# Almazny_channel.net
KiCad netlist of a schematic drawn in Altium Designer
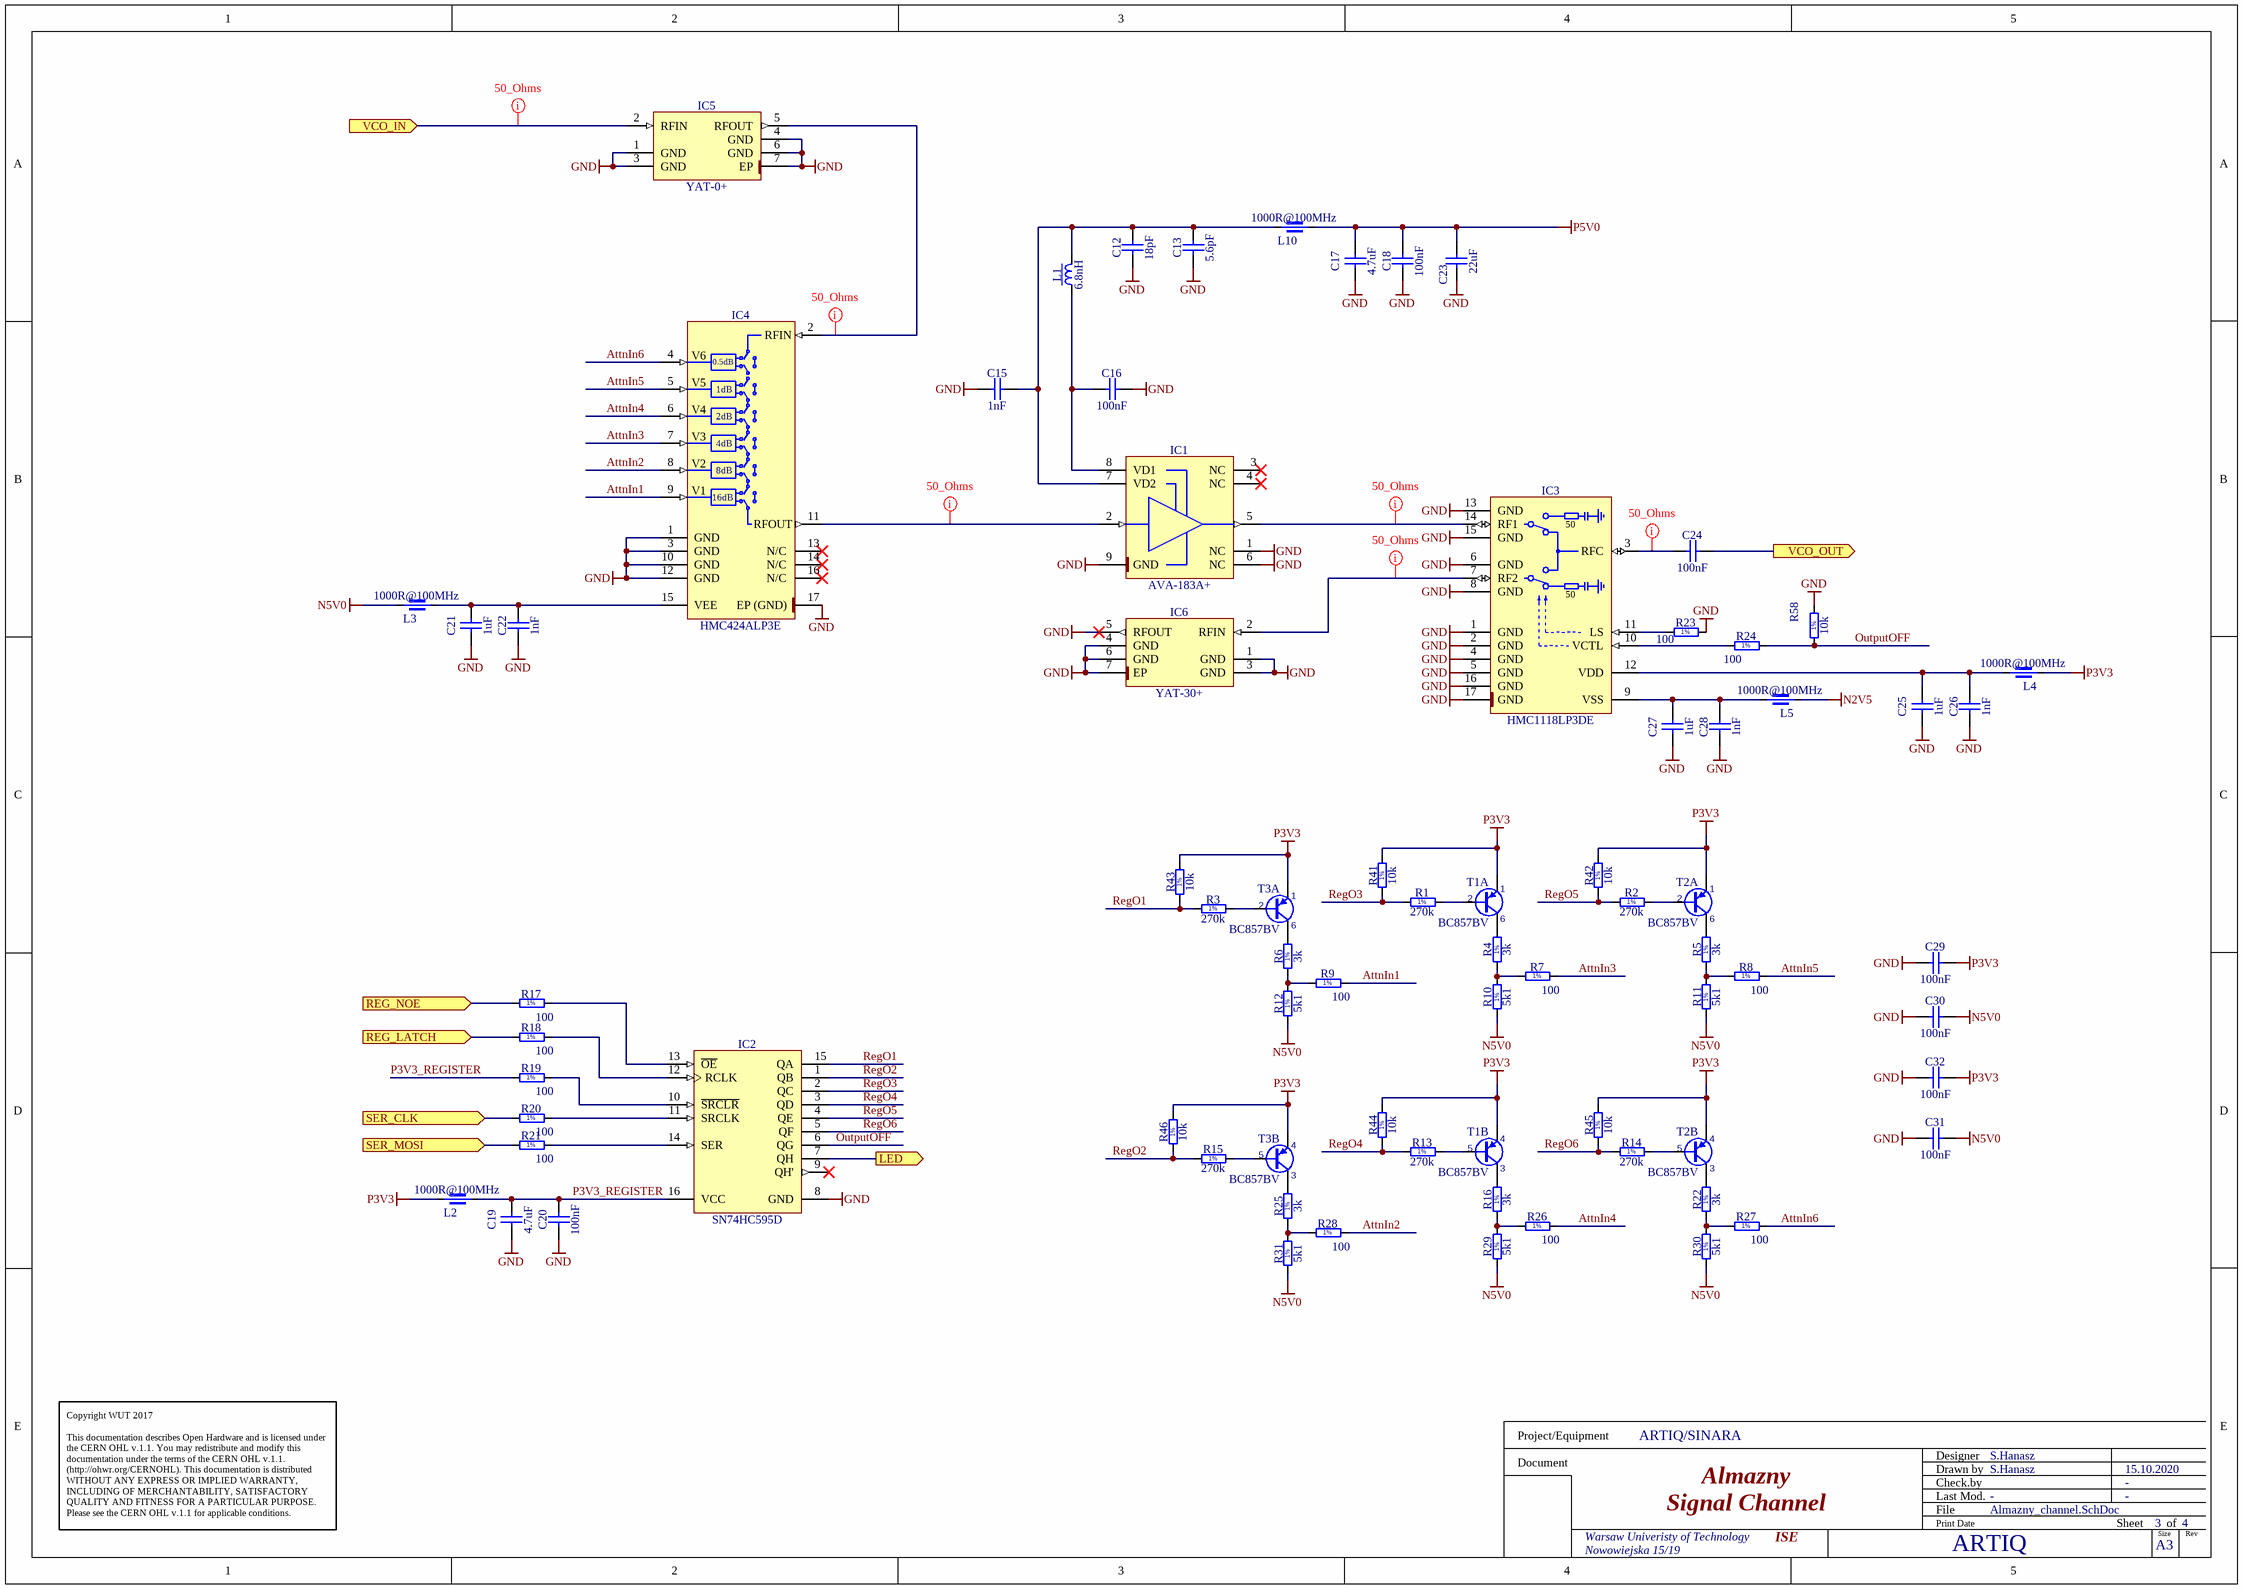
[diagram p0: Almazny_channel.SchDoc]

(export (version "E")
  (design (tool "Eeschema 10.0.6"))
  (components
    (comp (ref "C12")
      (value "18pF")
      (footprint "CAPC1005X55N")
      (description "Non-polarised capacitor")
      (fields
        (field (name "PART NUMBER") "CC0402_18PF_50V_5%_C0G")
        (field (name "VOLTAGE") "50V")
        (field (name "AUTHOR") "CERN DEM JLC")
      )
      (libsource (lib "Capacitors") (part "Capacitor - non polarized"))
    )
    (comp (ref "C13")
      (value "5.6pF")
      (footprint "CAPC1005X61N")
      (description "Non-polarised capacitor")
      (fields
        (field (name "PART NUMBER") "CC0402_5.6PF_50V_0.1PF_NP0_JOHANSON_R07S")
        (field (name "VOLTAGE") "50V")
        (field (name "AUTHOR") "CERN DEM MR")
      )
      (libsource (lib "Capacitors") (part "Capacitor - non polarized"))
    )
    (comp (ref "C15")
      (value "1nF")
      (footprint "CAPC1005X55N")
      (description "Non-polarised capacitor")
      (fields
        (field (name "PART NUMBER") "CC0402_1NF_50V_10%_X7R")
        (field (name "VOLTAGE") "50V")
        (field (name "AUTHOR") "CERN DEM JLC")
      )
      (libsource (lib "Capacitors") (part "Capacitor - non polarized"))
    )
    (comp (ref "C16")
      (value "100nF")
      (footprint "CAPC1005X55N")
      (description "Non-polarised capacitor")
      (fields
        (field (name "PART NUMBER") "CC0402_100NF_16V_10%_X5R")
        (field (name "VOLTAGE") "16V")
        (field (name "AUTHOR") "CERN DEM JLC")
      )
      (libsource (lib "Capacitors") (part "Capacitor - non polarized"))
    )
    (comp (ref "C17")
      (value "4.7uF")
      (footprint "CAPC1709X95N")
      (description "Non-polarised capacitor")
      (fields
        (field (name "MANUFACTURER") "GENERIC")
        (field (name "MANUFACTURER PART NUMBER") "CC0603_4.7UF_16V_10%_X5R")
        (field (name "AUTHOR") "CERN DEM JLC")
      )
      (libsource (lib "Capacitors") (part "Capacitor - non polarized"))
    )
    (comp (ref "C18")
      (value "100nF")
      (footprint "CAPC1005X55N")
      (description "Non-polarised capacitor")
      (fields
        (field (name "MANUFACTURER") "GENERIC")
        (field (name "MANUFACTURER PART NUMBER") "CC0402_100NF_16V_10%_X5R")
        (field (name "AUTHOR") "CERN DEM JLC")
      )
      (libsource (lib "Capacitors") (part "Capacitor - non polarized"))
    )
    (comp (ref "C19")
      (value "4.7uF")
      (footprint "CAPC1709X95N")
      (description "Non-polarised capacitor")
      (fields
        (field (name "MANUFACTURER") "GENERIC")
        (field (name "MANUFACTURER PART NUMBER") "CC0603_4.7UF_16V_10%_X5R")
        (field (name "AUTHOR") "CERN DEM JLC")
      )
      (libsource (lib "Capacitors") (part "Capacitor - non polarized"))
    )
    (comp (ref "C20")
      (value "100nF")
      (footprint "CAPC1005X55N")
      (description "Non-polarised capacitor")
      (fields
        (field (name "MANUFACTURER") "GENERIC")
        (field (name "MANUFACTURER PART NUMBER") "CC0402_100NF_16V_10%_X5R")
        (field (name "AUTHOR") "CERN DEM JLC")
      )
      (libsource (lib "Capacitors") (part "Capacitor - non polarized"))
    )
    (comp (ref "C21")
      (value "1uF")
      (footprint "CAPC1608X87N")
      (description "Non-polarised capacitor")
      (fields
        (field (name "MANUFACTURER") "GENERIC")
        (field (name "MANUFACTURER PART NUMBER") "CC0603_1UF_16V_10%_X7R")
        (field (name "AUTHOR") "CERN DEM JLC")
      )
      (libsource (lib "Capacitors") (part "Capacitor - non polarized"))
    )
    (comp (ref "C22")
      (value "1nF")
      (footprint "CAPC1005X55N")
      (description "Non-polarised capacitor")
      (fields
        (field (name "MANUFACTURER") "GENERIC")
        (field (name "MANUFACTURER PART NUMBER") "CC0402_1NF_50V_10%_X7R")
        (field (name "AUTHOR") "CERN DEM JLC")
      )
      (libsource (lib "Capacitors") (part "Capacitor - non polarized"))
    )
    (comp (ref "C23")
      (value "22uF")
      (footprint "CAPC2012X135N")
      (description "Non-polarised capacitor")
      (fields
        (field (name "PART NUMBER") "CC0805_22UF_16V_10%_X5R")
        (field (name "VOLTAGE") "16V")
        (field (name "AUTHOR") "CERN DEM JLC")
      )
      (libsource (lib "Capacitors") (part "Capacitor - non polarized"))
    )
    (comp (ref "C24")
      (value "100nF")
      (footprint "CAPC1005X70N")
      (description "Non-polarised capacitor")
      (fields
        (field (name "PART NUMBER") "CC0402_100NF_16V_10%_X7R_ATC_ATC530L")
        (field (name "VOLTAGE") "16V")
        (field (name "AUTHOR") "CERN DEM BC")
      )
      (libsource (lib "Capacitors") (part "Capacitor - non polarized"))
    )
    (comp (ref "C25")
      (value "1uF")
      (footprint "CAPC1608X87N")
      (description "Non-polarised capacitor")
      (fields
        (field (name "MANUFACTURER") "GENERIC")
        (field (name "MANUFACTURER PART NUMBER") "CC0603_1UF_16V_10%_X7R")
        (field (name "AUTHOR") "CERN DEM JLC")
      )
      (libsource (lib "Capacitors") (part "Capacitor - non polarized"))
    )
    (comp (ref "C26")
      (value "1nF")
      (footprint "CAPC1005X55N")
      (description "Non-polarised capacitor")
      (fields
        (field (name "MANUFACTURER") "GENERIC")
        (field (name "MANUFACTURER PART NUMBER") "CC0402_1NF_50V_10%_X7R")
        (field (name "AUTHOR") "CERN DEM JLC")
      )
      (libsource (lib "Capacitors") (part "Capacitor - non polarized"))
    )
    (comp (ref "C27")
      (value "1uF")
      (footprint "CAPC1608X87N")
      (description "Non-polarised capacitor")
      (fields
        (field (name "MANUFACTURER") "GENERIC")
        (field (name "MANUFACTURER PART NUMBER") "CC0603_1UF_16V_10%_X7R")
        (field (name "AUTHOR") "CERN DEM JLC")
      )
      (libsource (lib "Capacitors") (part "Capacitor - non polarized"))
    )
    (comp (ref "C28")
      (value "1nF")
      (footprint "CAPC1005X55N")
      (description "Non-polarised capacitor")
      (fields
        (field (name "MANUFACTURER") "GENERIC")
        (field (name "MANUFACTURER PART NUMBER") "CC0402_1NF_50V_10%_X7R")
        (field (name "AUTHOR") "CERN DEM JLC")
      )
      (libsource (lib "Capacitors") (part "Capacitor - non polarized"))
    )
    (comp (ref "C29")
      (value "100nF")
      (footprint "CAPC1005X55N")
      (description "Non-polarised capacitor")
      (fields
        (field (name "MANUFACTURER") "GENERIC")
        (field (name "MANUFACTURER PART NUMBER") "CC0402_100NF_16V_10%_X5R")
        (field (name "AUTHOR") "CERN DEM JLC")
      )
      (libsource (lib "Capacitors") (part "Capacitor - non polarized"))
    )
    (comp (ref "C30")
      (value "100nF")
      (footprint "CAPC1005X55N")
      (description "Non-polarised capacitor")
      (fields
        (field (name "MANUFACTURER") "GENERIC")
        (field (name "MANUFACTURER PART NUMBER") "CC0402_100NF_16V_10%_X5R")
        (field (name "AUTHOR") "CERN DEM JLC")
      )
      (libsource (lib "Capacitors") (part "Capacitor - non polarized"))
    )
    (comp (ref "C31")
      (value "100nF")
      (footprint "CAPC1005X55N")
      (description "Non-polarised capacitor")
      (fields
        (field (name "MANUFACTURER") "GENERIC")
        (field (name "MANUFACTURER PART NUMBER") "CC0402_100NF_16V_10%_X5R")
        (field (name "AUTHOR") "CERN DEM JLC")
      )
      (libsource (lib "Capacitors") (part "Capacitor - non polarized"))
    )
    (comp (ref "C32")
      (value "100nF")
      (footprint "CAPC1005X55N")
      (description "Non-polarised capacitor")
      (fields
        (field (name "MANUFACTURER") "GENERIC")
        (field (name "MANUFACTURER PART NUMBER") "CC0402_100NF_16V_10%_X5R")
        (field (name "AUTHOR") "CERN DEM JLC")
      )
      (libsource (lib "Capacitors") (part "Capacitor - non polarized"))
    )
    (comp (ref "IC1")
      (value "AVA-183A+")
      (footprint "MINI-CIRCUITS_DQ849")
      (description "5-18GHz, 50 Ohm Monolithic Amplifier")
      (fields (field (name "MANUFACTURER") "MINI-CIRCUITS") (field (name "AUTHOR") "CERN DEM JLC"))
      (libsource (lib "ICs And Semiconductors") (part "AVA-183A+"))
    )
    (comp (ref "IC2")
      (value "SN74HC595D")
      (footprint "SOIC127P600X175-16N")
      (description "8-Bit Shift Register With 3-State Output Register")
      (fields (field (name "MANUFACTURER") "TEXAS INSTRUMENTS") (field (name "AUTHOR") "CERN DEM JLC"))
      (libsource (lib "ICs And Semiconductors") (part "74595"))
    )
    (comp (ref "IC3")
      (value "HMC1118LP3DE")
      (footprint "QFN50P300X300X95-17N-S190")
      (description "High Isolation, Silicon SPDT, Non-Reflective Switch, 9 kHz to 13.0 GHz")
      (fields (field (name "MANUFACTURER") "ANALOG DEVICES") (field (name "AUTHOR") "CERN DEM MR"))
      (libsource (lib "ICs And Semiconductors") (part "HMC1118LP3DE"))
    )
    (comp (ref "IC4")
      (value "HMC424ALP3E")
      (footprint "QFN50P300X300X100-17N-S195")
      (description "0.5 dB LSB GaAs MMIC 6-BIT Digital Attenuator, DC - 13 GHz")
      (fields (field (name "MANUFACTURER") "ANALOG DEVICES") (field (name "AUTHOR") "CERN DEM BC"))
      (libsource (lib "ICs And Semiconductors") (part "HMC424ALP3E"))
    )
    (comp (ref "IC5")
      (value "YAT-0+")
      (footprint "MINI-CIRCUITS_MC1630")
      (description "DC to 18GHz, 2W, 50 Ohm, 0dB Attenuator")
      (fields (field (name "MANUFACTURER") "MINI-CIRCUITS") (field (name "AUTHOR") "CERN DEM JLC"))
      (libsource (lib "ICs And Semiconductors") (part "YAT-XX+"))
    )
    (comp (ref "IC6")
      (value "YAT-30+")
      (footprint "MINI-CIRCUITS_MC1630")
      (description "DC to 18GHz, 2W, 50 Ohm, 4dB Attenuator")
      (fields (field (name "MANUFACTURER") "MINI-CIRCUITS") (field (name "AUTHOR") "CERN DEM MR"))
      (libsource (lib "") (part "YAT-XX+_1"))
    )
    (comp (ref "L1")
      (value "6.8nH")
      (footprint "INDC2014X145N")
      (description "Inductor With Core")
      (fields
        (field (name "PART NUMBER") "IND0805_6.8NH_10%_EPCOS_B82498B")
        (field (name "POWER") "800mA")
        (field (name "AUTHOR") "CERN DEM JLC")
      )
      (libsource (lib "Inductors & Transformers") (part "Inductor With Magnetic core"))
    )
    (comp (ref "L2")
      (value "1000R@100MHz")
      (footprint "INDC1608X95N")
      (fields
        (field (name "MANUFACTURER") "MURATA")
        (field (name "MANUFACTURER PART NUMBER") "BLM18HE102SN1")
        (field (name "PART NUMBER") "IND0603_MURATA_BLM18HE102SN1")
        (field (name "AUTHOR") "CERN DEM JLC")
      )
      (libsource (lib "Inductors & Transformers") (part "Ferrite Bead"))
    )
    (comp (ref "L3")
      (value "1000R@100MHz")
      (footprint "INDC1608X95N")
      (fields
        (field (name "MANUFACTURER") "MURATA")
        (field (name "MANUFACTURER PART NUMBER") "BLM18HE102SN1")
        (field (name "PART NUMBER") "IND0603_MURATA_BLM18HE102SN1")
        (field (name "AUTHOR") "CERN DEM JLC")
      )
      (libsource (lib "Inductors & Transformers") (part "Ferrite Bead"))
    )
    (comp (ref "L4")
      (value "1000R@100MHz")
      (footprint "INDC1608X95N")
      (fields
        (field (name "MANUFACTURER") "MURATA")
        (field (name "MANUFACTURER PART NUMBER") "BLM18HE102SN1")
        (field (name "PART NUMBER") "IND0603_MURATA_BLM18HE102SN1")
        (field (name "AUTHOR") "CERN DEM JLC")
      )
      (libsource (lib "") (part "Ferrite Bead_1"))
    )
    (comp (ref "L5")
      (value "1000R@100MHz")
      (footprint "INDC1608X95N")
      (fields
        (field (name "MANUFACTURER") "MURATA")
        (field (name "MANUFACTURER PART NUMBER") "BLM18HE102SN1")
        (field (name "PART NUMBER") "IND0603_MURATA_BLM18HE102SN1")
        (field (name "AUTHOR") "CERN DEM JLC")
      )
      (libsource (lib "") (part "Ferrite Bead_1"))
    )
    (comp (ref "L10")
      (value "1000R@100MHz")
      (footprint "INDC1608X95N")
      (fields
        (field (name "MANUFACTURER") "MURATA")
        (field (name "MANUFACTURER PART NUMBER") "BLM18HE102SN1")
        (field (name "PART NUMBER") "IND0603_MURATA_BLM18HE102SN1")
        (field (name "AUTHOR") "CERN DEM JLC")
      )
      (libsource (lib "Inductors & Transformers") (part "Ferrite Bead"))
    )
    (comp (ref "R1")
      (value "270k")
      (footprint "RESC1005X40N")
      (description "Resistor - 1%")
      (fields
        (field (name "PART NUMBER") "R0402_270K_1%_0.0625W_100PPM")
        (field (name "POWER") "0.0625W")
        (field (name "AUTHOR") "CERN DEM JLC")
      )
      (libsource (lib "Resistors") (part "Resistor - 1%"))
    )
    (comp (ref "R2")
      (value "270k")
      (footprint "RESC1005X40N")
      (description "Resistor - 1%")
      (fields
        (field (name "PART NUMBER") "R0402_270K_1%_0.0625W_100PPM")
        (field (name "POWER") "0.0625W")
        (field (name "AUTHOR") "CERN DEM JLC")
      )
      (libsource (lib "Resistors") (part "Resistor - 1%"))
    )
    (comp (ref "R3")
      (value "270k")
      (footprint "RESC1005X40N")
      (description "Resistor - 1%")
      (fields
        (field (name "PART NUMBER") "R0402_270K_1%_0.0625W_100PPM")
        (field (name "POWER") "0.0625W")
        (field (name "AUTHOR") "CERN DEM JLC")
      )
      (libsource (lib "Resistors") (part "Resistor - 1%"))
    )
    (comp (ref "R4")
      (value "3k")
      (footprint "RESC1005X40N")
      (description "Resistor - 1%")
      (fields
        (field (name "PART NUMBER") "R0402_3K_1%_0.0625W_100PPM")
        (field (name "POWER") "0.0625W")
        (field (name "AUTHOR") "CERN DEM JLC")
      )
      (libsource (lib "Resistors") (part "Resistor - 1%"))
    )
    (comp (ref "R5")
      (value "3k")
      (footprint "RESC1005X40N")
      (description "Resistor - 1%")
      (fields
        (field (name "PART NUMBER") "R0402_3K_1%_0.0625W_100PPM")
        (field (name "POWER") "0.0625W")
        (field (name "AUTHOR") "CERN DEM JLC")
      )
      (libsource (lib "Resistors") (part "Resistor - 1%"))
    )
    (comp (ref "R6")
      (value "3k")
      (footprint "RESC1005X40N")
      (description "Resistor - 1%")
      (fields
        (field (name "PART NUMBER") "R0402_3K_1%_0.0625W_100PPM")
        (field (name "POWER") "0.0625W")
        (field (name "AUTHOR") "CERN DEM JLC")
      )
      (libsource (lib "Resistors") (part "Resistor - 1%"))
    )
    (comp (ref "R7")
      (value "100")
      (footprint "RESC1005X40N")
      (description "Resistor - 1%")
      (fields
        (field (name "PART NUMBER") "R0402_100R_1%_0.1W_100PPM")
        (field (name "POWER") "0.1W")
        (field (name "AUTHOR") "CERN DEM JLC")
      )
      (libsource (lib "Resistors") (part "Resistor - 1%"))
    )
    (comp (ref "R8")
      (value "100")
      (footprint "RESC1005X40N")
      (description "Resistor - 1%")
      (fields
        (field (name "PART NUMBER") "R0402_100R_1%_0.1W_100PPM")
        (field (name "POWER") "0.1W")
        (field (name "AUTHOR") "CERN DEM JLC")
      )
      (libsource (lib "Resistors") (part "Resistor - 1%"))
    )
    (comp (ref "R9")
      (value "100")
      (footprint "RESC1005X40N")
      (description "Resistor - 1%")
      (fields
        (field (name "PART NUMBER") "R0402_100R_1%_0.1W_100PPM")
        (field (name "POWER") "0.1W")
        (field (name "AUTHOR") "CERN DEM JLC")
      )
      (libsource (lib "Resistors") (part "Resistor - 1%"))
    )
    (comp (ref "R10")
      (value "5k1")
      (footprint "RESC1005X40N")
      (description "Resistor - 1%")
      (fields
        (field (name "PART NUMBER") "R0402_5K1_1%_0.0625W_100PPM")
        (field (name "POWER") "0.0625W")
        (field (name "AUTHOR") "CERN DEM JLC")
      )
      (libsource (lib "Resistors") (part "Resistor - 1%"))
    )
    (comp (ref "R11")
      (value "5k1")
      (footprint "RESC1005X40N")
      (description "Resistor - 1%")
      (fields
        (field (name "PART NUMBER") "R0402_5K1_1%_0.0625W_100PPM")
        (field (name "POWER") "0.0625W")
        (field (name "AUTHOR") "CERN DEM JLC")
      )
      (libsource (lib "Resistors") (part "Resistor - 1%"))
    )
    (comp (ref "R12")
      (value "5k1")
      (footprint "RESC1005X40N")
      (description "Resistor - 1%")
      (fields
        (field (name "PART NUMBER") "R0402_5K1_1%_0.0625W_100PPM")
        (field (name "POWER") "0.0625W")
        (field (name "AUTHOR") "CERN DEM JLC")
      )
      (libsource (lib "Resistors") (part "Resistor - 1%"))
    )
    (comp (ref "R13")
      (value "270k")
      (footprint "RESC1005X40N")
      (description "Resistor - 1%")
      (fields
        (field (name "PART NUMBER") "R0402_270K_1%_0.0625W_100PPM")
        (field (name "POWER") "0.0625W")
        (field (name "AUTHOR") "CERN DEM JLC")
      )
      (libsource (lib "Resistors") (part "Resistor - 1%"))
    )
    (comp (ref "R14")
      (value "270k")
      (footprint "RESC1005X40N")
      (description "Resistor - 1%")
      (fields
        (field (name "PART NUMBER") "R0402_270K_1%_0.0625W_100PPM")
        (field (name "POWER") "0.0625W")
        (field (name "AUTHOR") "CERN DEM JLC")
      )
      (libsource (lib "Resistors") (part "Resistor - 1%"))
    )
    (comp (ref "R15")
      (value "270k")
      (footprint "RESC1005X40N")
      (description "Resistor - 1%")
      (fields
        (field (name "PART NUMBER") "R0402_270K_1%_0.0625W_100PPM")
        (field (name "POWER") "0.0625W")
        (field (name "AUTHOR") "CERN DEM JLC")
      )
      (libsource (lib "Resistors") (part "Resistor - 1%"))
    )
    (comp (ref "R16")
      (value "3k")
      (footprint "RESC1005X40N")
      (description "Resistor - 1%")
      (fields
        (field (name "PART NUMBER") "R0402_3K_1%_0.0625W_100PPM")
        (field (name "POWER") "0.0625W")
        (field (name "AUTHOR") "CERN DEM JLC")
      )
      (libsource (lib "Resistors") (part "Resistor - 1%"))
    )
    (comp (ref "R17")
      (value "100")
      (footprint "RESC1005X40N")
      (description "Resistor - 1%")
      (fields
        (field (name "PART NUMBER") "R0402_100R_1%_0.1W_100PPM")
        (field (name "POWER") "0.1W")
        (field (name "AUTHOR") "CERN DEM JLC")
      )
      (libsource (lib "Resistors") (part "Resistor - 1%"))
    )
    (comp (ref "R18")
      (value "100")
      (footprint "RESC1005X40N")
      (description "Resistor - 1%")
      (fields
        (field (name "PART NUMBER") "R0402_100R_1%_0.1W_100PPM")
        (field (name "POWER") "0.1W")
        (field (name "AUTHOR") "CERN DEM JLC")
      )
      (libsource (lib "Resistors") (part "Resistor - 1%"))
    )
    (comp (ref "R19")
      (value "100")
      (footprint "RESC1005X40N")
      (description "Resistor - 1%")
      (fields
        (field (name "PART NUMBER") "R0402_100R_1%_0.1W_100PPM")
        (field (name "POWER") "0.1W")
        (field (name "AUTHOR") "CERN DEM JLC")
      )
      (libsource (lib "Resistors") (part "Resistor - 1%"))
    )
    (comp (ref "R20")
      (value "100")
      (footprint "RESC1005X40N")
      (description "Resistor - 1%")
      (fields
        (field (name "PART NUMBER") "R0402_100R_1%_0.1W_100PPM")
        (field (name "POWER") "0.1W")
        (field (name "AUTHOR") "CERN DEM JLC")
      )
      (libsource (lib "Resistors") (part "Resistor - 1%"))
    )
    (comp (ref "R21")
      (value "100")
      (footprint "RESC1005X40N")
      (description "Resistor - 1%")
      (fields
        (field (name "PART NUMBER") "R0402_100R_1%_0.1W_100PPM")
        (field (name "POWER") "0.1W")
        (field (name "AUTHOR") "CERN DEM JLC")
      )
      (libsource (lib "Resistors") (part "Resistor - 1%"))
    )
    (comp (ref "R22")
      (value "3k")
      (footprint "RESC1005X40N")
      (description "Resistor - 1%")
      (fields
        (field (name "PART NUMBER") "R0402_3K_1%_0.0625W_100PPM")
        (field (name "POWER") "0.0625W")
        (field (name "AUTHOR") "CERN DEM JLC")
      )
      (libsource (lib "Resistors") (part "Resistor - 1%"))
    )
    (comp (ref "R23")
      (value "100")
      (footprint "RESC1005X40N")
      (description "Resistor - 1%")
      (fields
        (field (name "PART NUMBER") "R0402_100R_1%_0.1W_100PPM")
        (field (name "POWER") "0.1W")
        (field (name "AUTHOR") "CERN DEM JLC")
      )
      (libsource (lib "Resistors") (part "Resistor - 1%"))
    )
    (comp (ref "R24")
      (value "100")
      (footprint "RESC1005X40N")
      (description "Resistor - 1%")
      (fields
        (field (name "PART NUMBER") "R0402_100R_1%_0.1W_100PPM")
        (field (name "POWER") "0.1W")
        (field (name "AUTHOR") "CERN DEM JLC")
      )
      (libsource (lib "Resistors") (part "Resistor - 1%"))
    )
    (comp (ref "R25")
      (value "3k")
      (footprint "RESC1005X40N")
      (description "Resistor - 1%")
      (fields
        (field (name "PART NUMBER") "R0402_3K_1%_0.0625W_100PPM")
        (field (name "POWER") "0.0625W")
        (field (name "AUTHOR") "CERN DEM JLC")
      )
      (libsource (lib "Resistors") (part "Resistor - 1%"))
    )
    (comp (ref "R26")
      (value "100")
      (footprint "RESC1005X40N")
      (description "Resistor - 1%")
      (fields
        (field (name "PART NUMBER") "R0402_100R_1%_0.1W_100PPM")
        (field (name "POWER") "0.1W")
        (field (name "AUTHOR") "CERN DEM JLC")
      )
      (libsource (lib "Resistors") (part "Resistor - 1%"))
    )
    (comp (ref "R27")
      (value "100")
      (footprint "RESC1005X40N")
      (description "Resistor - 1%")
      (fields
        (field (name "PART NUMBER") "R0402_100R_1%_0.1W_100PPM")
        (field (name "POWER") "0.1W")
        (field (name "AUTHOR") "CERN DEM JLC")
      )
      (libsource (lib "Resistors") (part "Resistor - 1%"))
    )
    (comp (ref "R28")
      (value "100")
      (footprint "RESC1005X40N")
      (description "Resistor - 1%")
      (fields
        (field (name "PART NUMBER") "R0402_100R_1%_0.1W_100PPM")
        (field (name "POWER") "0.1W")
        (field (name "AUTHOR") "CERN DEM JLC")
      )
      (libsource (lib "Resistors") (part "Resistor - 1%"))
    )
    (comp (ref "R29")
      (value "5k1")
      (footprint "RESC1005X40N")
      (description "Resistor - 1%")
      (fields
        (field (name "PART NUMBER") "R0402_5K1_1%_0.0625W_100PPM")
        (field (name "POWER") "0.0625W")
        (field (name "AUTHOR") "CERN DEM JLC")
      )
      (libsource (lib "Resistors") (part "Resistor - 1%"))
    )
    (comp (ref "R30")
      (value "5k1")
      (footprint "RESC1005X40N")
      (description "Resistor - 1%")
      (fields
        (field (name "PART NUMBER") "R0402_5K1_1%_0.0625W_100PPM")
        (field (name "POWER") "0.0625W")
        (field (name "AUTHOR") "CERN DEM JLC")
      )
      (libsource (lib "Resistors") (part "Resistor - 1%"))
    )
    (comp (ref "R31")
      (value "5k1")
      (footprint "RESC1005X40N")
      (description "Resistor - 1%")
      (fields
        (field (name "PART NUMBER") "R0402_5K1_1%_0.0625W_100PPM")
        (field (name "POWER") "0.0625W")
        (field (name "AUTHOR") "CERN DEM JLC")
      )
      (libsource (lib "Resistors") (part "Resistor - 1%"))
    )
    (comp (ref "R41")
      (value "10k")
      (footprint "RESC1005X40N")
      (description "Resistor - 1%")
      (fields
        (field (name "PART NUMBER") "R0402_10K_1%_0.0625W_100PPM")
        (field (name "POWER") "0.0625W")
        (field (name "AUTHOR") "CERN DEM JLC")
      )
      (libsource (lib "Resistors") (part "Resistor - 1%"))
    )
    (comp (ref "R42")
      (value "10k")
      (footprint "RESC1005X40N")
      (description "Resistor - 1%")
      (fields
        (field (name "PART NUMBER") "R0402_10K_1%_0.0625W_100PPM")
        (field (name "POWER") "0.0625W")
        (field (name "AUTHOR") "CERN DEM JLC")
      )
      (libsource (lib "Resistors") (part "Resistor - 1%"))
    )
    (comp (ref "R43")
      (value "10k")
      (footprint "RESC1005X40N")
      (description "Resistor - 1%")
      (fields
        (field (name "PART NUMBER") "R0402_10K_1%_0.0625W_100PPM")
        (field (name "POWER") "0.0625W")
        (field (name "AUTHOR") "CERN DEM JLC")
      )
      (libsource (lib "Resistors") (part "Resistor - 1%"))
    )
    (comp (ref "R44")
      (value "10k")
      (footprint "RESC1005X40N")
      (description "Resistor - 1%")
      (fields
        (field (name "PART NUMBER") "R0402_10K_1%_0.0625W_100PPM")
        (field (name "POWER") "0.0625W")
        (field (name "AUTHOR") "CERN DEM JLC")
      )
      (libsource (lib "Resistors") (part "Resistor - 1%"))
    )
    (comp (ref "R45")
      (value "10k")
      (footprint "RESC1005X40N")
      (description "Resistor - 1%")
      (fields
        (field (name "PART NUMBER") "R0402_10K_1%_0.0625W_100PPM")
        (field (name "POWER") "0.0625W")
        (field (name "AUTHOR") "CERN DEM JLC")
      )
      (libsource (lib "Resistors") (part "Resistor - 1%"))
    )
    (comp (ref "R46")
      (value "10k")
      (footprint "RESC1005X40N")
      (description "Resistor - 1%")
      (fields
        (field (name "PART NUMBER") "R0402_10K_1%_0.0625W_100PPM")
        (field (name "POWER") "0.0625W")
        (field (name "AUTHOR") "CERN DEM JLC")
      )
      (libsource (lib "Resistors") (part "Resistor - 1%"))
    )
    (comp (ref "R58")
      (value "10k")
      (footprint "RESC1005X40N")
      (description "Resistor - 1%")
      (fields
        (field (name "PART NUMBER") "R0402_10K_1%_0.0625W_100PPM")
        (field (name "POWER") "0.0625W")
        (field (name "AUTHOR") "CERN DEM JLC")
      )
      (libsource (lib "Resistors") (part "Resistor - 1%"))
    )
    (comp (ref "T1")
      (value "BC857BV")
      (footprint "SOTFL50P160X60-6N")
      (description "45V, 100mA PNP General Purpose Double Transistor")
      (fields (field (name "MANUFACTURER") "NXP SEMICONDUCTORS") (field (name "AUTHOR") "CERN DEM JLC"))
      (libsource (lib "ICs And Semiconductors") (part "BC857BV"))
    )
    (comp (ref "T2")
      (value "BC857BV")
      (footprint "SOTFL50P160X60-6N")
      (description "45V, 100mA PNP General Purpose Double Transistor")
      (fields (field (name "MANUFACTURER") "NXP SEMICONDUCTORS") (field (name "AUTHOR") "CERN DEM JLC"))
      (libsource (lib "ICs And Semiconductors") (part "BC857BV"))
    )
    (comp (ref "T3")
      (value "BC857BV")
      (footprint "SOTFL50P160X60-6N")
      (description "45V, 100mA PNP General Purpose Double Transistor")
      (fields (field (name "MANUFACTURER") "NXP SEMICONDUCTORS") (field (name "AUTHOR") "CERN DEM JLC"))
      (libsource (lib "ICs And Semiconductors") (part "BC857BV"))
    )
  )
  (nets
    (net (code "1") (name "/AttnIn1") (class "Default")
      (node (ref "IC4") (pin "9") (pinfunction "V1_9") (pintype "input"))
      (node (ref "R9") (pin "2") (pinfunction "2_2") (pintype "passive"))
    )
    (net (code "2") (name "/AttnIn2") (class "Default")
      (node (ref "IC4") (pin "8") (pinfunction "V2_8") (pintype "input"))
      (node (ref "R28") (pin "2") (pinfunction "2_2") (pintype "passive"))
    )
    (net (code "3") (name "/AttnIn3") (class "Default")
      (node (ref "IC4") (pin "7") (pinfunction "V3_7") (pintype "input"))
      (node (ref "R7") (pin "2") (pinfunction "2_2") (pintype "passive"))
    )
    (net (code "4") (name "/AttnIn4") (class "Default")
      (node (ref "IC4") (pin "6") (pinfunction "V4_6") (pintype "input"))
      (node (ref "R26") (pin "2") (pinfunction "2_2") (pintype "passive"))
    )
    (net (code "5") (name "/AttnIn5") (class "Default")
      (node (ref "IC4") (pin "5") (pinfunction "V5_5") (pintype "input"))
      (node (ref "R8") (pin "2") (pinfunction "2_2") (pintype "passive"))
    )
    (net (code "6") (name "/AttnIn6") (class "Default")
      (node (ref "IC4") (pin "4") (pinfunction "V6_4") (pintype "input"))
      (node (ref "R27") (pin "2") (pinfunction "2_2") (pintype "passive"))
    )
    (net (code "7") (name "/LED") (class "Default")
      (node (ref "IC2") (pin "7") (pinfunction "QH_7") (pintype "tri_state"))
    )
    (net (code "8") (name "/OutputOFF") (class "Default")
      (node (ref "IC2") (pin "6") (pinfunction "QG_6") (pintype "tri_state"))
      (node (ref "R24") (pin "1") (pinfunction "1_1") (pintype "passive"))
      (node (ref "R58") (pin "1") (pinfunction "1_1") (pintype "passive"))
    )
    (net (code "9") (name "/P3V3_REGISTER") (class "Default")
      (node (ref "C19") (pin "2") (pinfunction "2_2") (pintype "passive"))
      (node (ref "C20") (pin "2") (pinfunction "2_2") (pintype "passive"))
      (node (ref "IC2") (pin "16") (pinfunction "VCC_16") (pintype "power_in"))
      (node (ref "L2") (pin "2") (pinfunction "2_2") (pintype "passive"))
      (node (ref "R19") (pin "1") (pinfunction "1_1") (pintype "passive"))
    )
    (net (code "10") (name "/REG_LATCH") (class "Default")
      (node (ref "R18") (pin "1") (pinfunction "1_1") (pintype "passive"))
    )
    (net (code "11") (name "/REG_NOE") (class "Default")
      (node (ref "R17") (pin "1") (pinfunction "1_1") (pintype "passive"))
    )
    (net (code "12") (name "/RegO1") (class "Default")
      (node (ref "IC2") (pin "15") (pinfunction "QA_15") (pintype "tri_state"))
      (node (ref "R3") (pin "1") (pinfunction "1_1") (pintype "passive"))
      (node (ref "R43") (pin "1") (pinfunction "1_1") (pintype "passive"))
    )
    (net (code "13") (name "/RegO2") (class "Default")
      (node (ref "IC2") (pin "1") (pinfunction "QB_1") (pintype "tri_state"))
      (node (ref "R15") (pin "1") (pinfunction "1_1") (pintype "passive"))
      (node (ref "R46") (pin "1") (pinfunction "1_1") (pintype "passive"))
    )
    (net (code "14") (name "/RegO3") (class "Default")
      (node (ref "IC2") (pin "2") (pinfunction "QC_2") (pintype "tri_state"))
      (node (ref "R1") (pin "1") (pinfunction "1_1") (pintype "passive"))
      (node (ref "R41") (pin "1") (pinfunction "1_1") (pintype "passive"))
    )
    (net (code "15") (name "/RegO4") (class "Default")
      (node (ref "IC2") (pin "3") (pinfunction "QD_3") (pintype "tri_state"))
      (node (ref "R13") (pin "1") (pinfunction "1_1") (pintype "passive"))
      (node (ref "R44") (pin "1") (pinfunction "1_1") (pintype "passive"))
    )
    (net (code "16") (name "/RegO5") (class "Default")
      (node (ref "IC2") (pin "4") (pinfunction "QE_4") (pintype "tri_state"))
      (node (ref "R2") (pin "1") (pinfunction "1_1") (pintype "passive"))
      (node (ref "R42") (pin "1") (pinfunction "1_1") (pintype "passive"))
    )
    (net (code "17") (name "/RegO6") (class "Default")
      (node (ref "IC2") (pin "5") (pinfunction "QF_5") (pintype "tri_state"))
      (node (ref "R14") (pin "1") (pinfunction "1_1") (pintype "passive"))
      (node (ref "R45") (pin "1") (pinfunction "1_1") (pintype "passive"))
    )
    (net (code "18") (name "/SER_CLK") (class "Default")
      (node (ref "R20") (pin "1") (pinfunction "1_1") (pintype "passive"))
    )
    (net (code "19") (name "/SER_MOSI") (class "Default")
      (node (ref "R21") (pin "1") (pinfunction "1_1") (pintype "passive"))
    )
    (net (code "20") (name "/VCO_IN") (class "Default")
      (node (ref "IC5") (pin "2") (pinfunction "RFIN_2") (pintype "input"))
    )
    (net (code "21") (name "/VCO_OUT") (class "Default")
      (node (ref "C24") (pin "2") (pinfunction "2_2") (pintype "passive"))
    )
    (net (code "22") (name "GND") (class "Default")
      (node (ref "C12") (pin "1") (pinfunction "1_1") (pintype "passive"))
      (node (ref "C13") (pin "1") (pinfunction "1_1") (pintype "passive"))
      (node (ref "C15") (pin "1") (pinfunction "1_1") (pintype "passive"))
      (node (ref "C16") (pin "2") (pinfunction "2_2") (pintype "passive"))
      (node (ref "C17") (pin "1") (pinfunction "1_1") (pintype "passive"))
      (node (ref "C18") (pin "1") (pinfunction "1_1") (pintype "passive"))
      (node (ref "C19") (pin "1") (pinfunction "1_1") (pintype "passive"))
      (node (ref "C20") (pin "1") (pinfunction "1_1") (pintype "passive"))
      (node (ref "C21") (pin "1") (pinfunction "1_1") (pintype "passive"))
      (node (ref "C22") (pin "1") (pinfunction "1_1") (pintype "passive"))
      (node (ref "C23") (pin "1") (pinfunction "1_1") (pintype "passive"))
      (node (ref "C25") (pin "1") (pinfunction "1_1") (pintype "passive"))
      (node (ref "C26") (pin "1") (pinfunction "1_1") (pintype "passive"))
      (node (ref "C27") (pin "1") (pinfunction "1_1") (pintype "passive"))
      (node (ref "C28") (pin "1") (pinfunction "1_1") (pintype "passive"))
      (node (ref "C29") (pin "1") (pinfunction "1_1") (pintype "passive"))
      (node (ref "C30") (pin "1") (pinfunction "1_1") (pintype "passive"))
      (node (ref "C31") (pin "1") (pinfunction "1_1") (pintype "passive"))
      (node (ref "C32") (pin "1") (pinfunction "1_1") (pintype "passive"))
      (node (ref "IC1") (pin "1") (pinfunction "NC_1") (pintype "passive"))
      (node (ref "IC1") (pin "6") (pinfunction "NC_6") (pintype "passive"))
      (node (ref "IC1") (pin "9") (pinfunction "GND_9") (pintype "power_in"))
      (node (ref "IC2") (pin "8") (pinfunction "GND_8") (pintype "power_in"))
      (node (ref "IC3") (pin "1") (pinfunction "GND_1") (pintype "power_in"))
      (node (ref "IC3") (pin "13") (pinfunction "GND_13") (pintype "power_in"))
      (node (ref "IC3") (pin "15") (pinfunction "GND_15") (pintype "power_in"))
      (node (ref "IC3") (pin "16") (pinfunction "GND_16") (pintype "power_in"))
      (node (ref "IC3") (pin "17") (pinfunction "GND_17") (pintype "power_in"))
      (node (ref "IC3") (pin "2") (pinfunction "GND_2") (pintype "power_in"))
      (node (ref "IC3") (pin "4") (pinfunction "GND_4") (pintype "power_in"))
      (node (ref "IC3") (pin "5") (pinfunction "GND_5") (pintype "power_in"))
      (node (ref "IC3") (pin "6") (pinfunction "GND_6") (pintype "power_in"))
      (node (ref "IC3") (pin "8") (pinfunction "GND_8") (pintype "power_in"))
      (node (ref "IC4") (pin "1") (pinfunction "GND_1") (pintype "power_in"))
      (node (ref "IC4") (pin "10") (pinfunction "GND_10") (pintype "power_in"))
      (node (ref "IC4") (pin "12") (pinfunction "GND_12") (pintype "power_in"))
      (node (ref "IC4") (pin "17") (pinfunction "EP_(GND)_17") (pintype "power_in"))
      (node (ref "IC4") (pin "3") (pinfunction "GND_3") (pintype "power_in"))
      (node (ref "IC5") (pin "1") (pinfunction "GND_1") (pintype "power_in"))
      (node (ref "IC5") (pin "3") (pinfunction "GND_3") (pintype "power_in"))
      (node (ref "IC5") (pin "4") (pinfunction "GND_4") (pintype "power_in"))
      (node (ref "IC5") (pin "6") (pinfunction "GND_6") (pintype "power_in"))
      (node (ref "IC5") (pin "7") (pinfunction "EP_7") (pintype "power_in"))
      (node (ref "IC6") (pin "1") (pinfunction "GND_1") (pintype "power_in"))
      (node (ref "IC6") (pin "3") (pinfunction "GND_3") (pintype "power_in"))
      (node (ref "IC6") (pin "4") (pinfunction "GND_4") (pintype "power_in"))
      (node (ref "IC6") (pin "5") (pinfunction "RFOUT_5") (pintype "output"))
      (node (ref "IC6") (pin "6") (pinfunction "GND_6") (pintype "power_in"))
      (node (ref "IC6") (pin "7") (pinfunction "EP_7") (pintype "power_in"))
      (node (ref "R23") (pin "1") (pinfunction "1_1") (pintype "passive"))
      (node (ref "R58") (pin "2") (pinfunction "2_2") (pintype "passive"))
    )
    (net (code "23") (name "N2V5") (class "Default")
      (node (ref "L5") (pin "1") (pinfunction "1_1") (pintype "passive"))
    )
    (net (code "24") (name "N5V0") (class "Default")
      (node (ref "C30") (pin "2") (pinfunction "2_2") (pintype "passive"))
      (node (ref "C31") (pin "2") (pinfunction "2_2") (pintype "passive"))
      (node (ref "L3") (pin "1") (pinfunction "1_1") (pintype "passive"))
      (node (ref "R10") (pin "1") (pinfunction "1_1") (pintype "passive"))
      (node (ref "R11") (pin "1") (pinfunction "1_1") (pintype "passive"))
      (node (ref "R12") (pin "1") (pinfunction "1_1") (pintype "passive"))
      (node (ref "R29") (pin "1") (pinfunction "1_1") (pintype "passive"))
      (node (ref "R30") (pin "1") (pinfunction "1_1") (pintype "passive"))
      (node (ref "R31") (pin "1") (pinfunction "1_1") (pintype "passive"))
    )
    (net (code "25") (name "Net-(IC1-RF_IN)") (class "Default")
      (node (ref "IC1") (pin "2") (pinfunction "RF_IN_2") (pintype "input"))
      (node (ref "IC4") (pin "11") (pinfunction "RFOUT_11") (pintype "output"))
    )
    (net (code "26") (name "Net-(IC1-RF_OUT)") (class "Default")
      (node (ref "IC1") (pin "5") (pinfunction "RF_OUT_5") (pintype "output"))
      (node (ref "IC3") (pin "14") (pinfunction "RF1_14") (pintype "bidirectional"))
    )
    (net (code "27") (name "Net-(IC1-VD1)") (class "Default")
      (node (ref "C16") (pin "1") (pinfunction "1_1") (pintype "passive"))
      (node (ref "IC1") (pin "8") (pinfunction "VD1_8") (pintype "power_in"))
      (node (ref "L1") (pin "1") (pinfunction "1_1") (pintype "passive"))
    )
    (net (code "28") (name "Net-(IC1-VD2)") (class "Default")
      (node (ref "C12") (pin "2") (pinfunction "2_2") (pintype "passive"))
      (node (ref "C13") (pin "2") (pinfunction "2_2") (pintype "passive"))
      (node (ref "C15") (pin "2") (pinfunction "2_2") (pintype "passive"))
      (node (ref "IC1") (pin "7") (pinfunction "VD2_7") (pintype "power_in"))
      (node (ref "L1") (pin "2") (pinfunction "2_2") (pintype "passive"))
      (node (ref "L10") (pin "1") (pinfunction "1_1") (pintype "passive"))
    )
    (net (code "29") (name "Net-(IC2-RCLK)") (class "Default")
      (node (ref "IC2") (pin "12") (pinfunction "RCLK_12") (pintype "input"))
      (node (ref "R18") (pin "2") (pinfunction "2_2") (pintype "passive"))
    )
    (net (code "30") (name "Net-(IC2-SER)") (class "Default")
      (node (ref "IC2") (pin "14") (pinfunction "SER_14") (pintype "input"))
      (node (ref "R21") (pin "2") (pinfunction "2_2") (pintype "passive"))
    )
    (net (code "31") (name "Net-(IC2-SRCLK)") (class "Default")
      (node (ref "IC2") (pin "11") (pinfunction "SRCLK_11") (pintype "input"))
      (node (ref "R20") (pin "2") (pinfunction "2_2") (pintype "passive"))
    )
    (net (code "32") (name "Net-(IC2-~{OE})") (class "Default")
      (node (ref "IC2") (pin "13") (pinfunction "~{OE}_13") (pintype "input"))
      (node (ref "R17") (pin "2") (pinfunction "2_2") (pintype "passive"))
    )
    (net (code "33") (name "Net-(IC2-~{SRCLR})") (class "Default")
      (node (ref "IC2") (pin "10") (pinfunction "~{SRCLR}_10") (pintype "input"))
      (node (ref "R19") (pin "2") (pinfunction "2_2") (pintype "passive"))
    )
    (net (code "34") (name "Net-(IC3-LS)") (class "Default")
      (node (ref "IC3") (pin "11") (pinfunction "LS_11") (pintype "input"))
      (node (ref "R23") (pin "2") (pinfunction "2_2") (pintype "passive"))
    )
    (net (code "35") (name "Net-(IC3-RF2)") (class "Default")
      (node (ref "IC3") (pin "7") (pinfunction "RF2_7") (pintype "bidirectional"))
      (node (ref "IC6") (pin "2") (pinfunction "RFIN_2") (pintype "input"))
    )
    (net (code "36") (name "Net-(IC3-RFC)") (class "Default")
      (node (ref "C24") (pin "1") (pinfunction "1_1") (pintype "passive"))
      (node (ref "IC3") (pin "3") (pinfunction "RFC_3") (pintype "bidirectional"))
    )
    (net (code "37") (name "Net-(IC3-VCTL)") (class "Default")
      (node (ref "IC3") (pin "10") (pinfunction "VCTL_10") (pintype "input"))
      (node (ref "R24") (pin "2") (pinfunction "2_2") (pintype "passive"))
    )
    (net (code "38") (name "Net-(IC3-VDD)") (class "Default")
      (node (ref "C25") (pin "2") (pinfunction "2_2") (pintype "passive"))
      (node (ref "C26") (pin "2") (pinfunction "2_2") (pintype "passive"))
      (node (ref "IC3") (pin "12") (pinfunction "VDD_12") (pintype "power_in"))
      (node (ref "L4") (pin "2") (pinfunction "2_2") (pintype "passive"))
    )
    (net (code "39") (name "Net-(IC3-VSS)") (class "Default")
      (node (ref "C27") (pin "2") (pinfunction "2_2") (pintype "passive"))
      (node (ref "C28") (pin "2") (pinfunction "2_2") (pintype "passive"))
      (node (ref "IC3") (pin "9") (pinfunction "VSS_9") (pintype "power_in"))
      (node (ref "L5") (pin "2") (pinfunction "2_2") (pintype "passive"))
    )
    (net (code "40") (name "Net-(IC4-RFIN)") (class "Default")
      (node (ref "IC4") (pin "2") (pinfunction "RFIN_2") (pintype "input"))
      (node (ref "IC5") (pin "5") (pinfunction "RFOUT_5") (pintype "output"))
    )
    (net (code "41") (name "Net-(IC4-VEE)") (class "Default")
      (node (ref "C21") (pin "2") (pinfunction "2_2") (pintype "passive"))
      (node (ref "C22") (pin "2") (pinfunction "2_2") (pintype "passive"))
      (node (ref "IC4") (pin "15") (pinfunction "VEE_15") (pintype "power_in"))
      (node (ref "L3") (pin "2") (pinfunction "2_2") (pintype "passive"))
    )
    (net (code "42") (name "Net-(R10-Pad2)") (class "Default")
      (node (ref "R10") (pin "2") (pinfunction "2_2") (pintype "passive"))
      (node (ref "R4") (pin "1") (pinfunction "1_1") (pintype "passive"))
      (node (ref "R7") (pin "1") (pinfunction "1_1") (pintype "passive"))
    )
    (net (code "43") (name "Net-(R11-Pad2)") (class "Default")
      (node (ref "R11") (pin "2") (pinfunction "2_2") (pintype "passive"))
      (node (ref "R5") (pin "1") (pinfunction "1_1") (pintype "passive"))
      (node (ref "R8") (pin "1") (pinfunction "1_1") (pintype "passive"))
    )
    (net (code "44") (name "Net-(R12-Pad2)") (class "Default")
      (node (ref "R12") (pin "2") (pinfunction "2_2") (pintype "passive"))
      (node (ref "R6") (pin "1") (pinfunction "1_1") (pintype "passive"))
      (node (ref "R9") (pin "1") (pinfunction "1_1") (pintype "passive"))
    )
    (net (code "45") (name "Net-(R16-Pad1)") (class "Default")
      (node (ref "R16") (pin "1") (pinfunction "1_1") (pintype "passive"))
      (node (ref "R26") (pin "1") (pinfunction "1_1") (pintype "passive"))
      (node (ref "R29") (pin "2") (pinfunction "2_2") (pintype "passive"))
    )
    (net (code "46") (name "Net-(R22-Pad1)") (class "Default")
      (node (ref "R22") (pin "1") (pinfunction "1_1") (pintype "passive"))
      (node (ref "R27") (pin "1") (pinfunction "1_1") (pintype "passive"))
      (node (ref "R30") (pin "2") (pinfunction "2_2") (pintype "passive"))
    )
    (net (code "47") (name "Net-(R25-Pad1)") (class "Default")
      (node (ref "R25") (pin "1") (pinfunction "1_1") (pintype "passive"))
      (node (ref "R28") (pin "1") (pinfunction "1_1") (pintype "passive"))
      (node (ref "R31") (pin "2") (pinfunction "2_2") (pintype "passive"))
    )
    (net (code "48") (name "Net-(T1A-B)") (class "Default")
      (node (ref "R1") (pin "2") (pinfunction "2_2") (pintype "passive"))
      (node (ref "T1") (pin "2") (pinfunction "B_2") (pintype "passive"))
    )
    (net (code "49") (name "Net-(T1A-C)") (class "Default")
      (node (ref "R4") (pin "2") (pinfunction "2_2") (pintype "passive"))
      (node (ref "T1") (pin "6") (pinfunction "C_6") (pintype "passive"))
    )
    (net (code "50") (name "Net-(T1B-B)") (class "Default")
      (node (ref "R13") (pin "2") (pinfunction "2_2") (pintype "passive"))
      (node (ref "T1") (pin "5") (pinfunction "B_5") (pintype "passive"))
    )
    (net (code "51") (name "Net-(T1B-C)") (class "Default")
      (node (ref "R16") (pin "2") (pinfunction "2_2") (pintype "passive"))
      (node (ref "T1") (pin "3") (pinfunction "C_3") (pintype "passive"))
    )
    (net (code "52") (name "Net-(T2A-B)") (class "Default")
      (node (ref "R2") (pin "2") (pinfunction "2_2") (pintype "passive"))
      (node (ref "T2") (pin "2") (pinfunction "B_2") (pintype "passive"))
    )
    (net (code "53") (name "Net-(T2A-C)") (class "Default")
      (node (ref "R5") (pin "2") (pinfunction "2_2") (pintype "passive"))
      (node (ref "T2") (pin "6") (pinfunction "C_6") (pintype "passive"))
    )
    (net (code "54") (name "Net-(T2B-B)") (class "Default")
      (node (ref "R14") (pin "2") (pinfunction "2_2") (pintype "passive"))
      (node (ref "T2") (pin "5") (pinfunction "B_5") (pintype "passive"))
    )
    (net (code "55") (name "Net-(T2B-C)") (class "Default")
      (node (ref "R22") (pin "2") (pinfunction "2_2") (pintype "passive"))
      (node (ref "T2") (pin "3") (pinfunction "C_3") (pintype "passive"))
    )
    (net (code "56") (name "Net-(T3A-B)") (class "Default")
      (node (ref "R3") (pin "2") (pinfunction "2_2") (pintype "passive"))
      (node (ref "T3") (pin "2") (pinfunction "B_2") (pintype "passive"))
    )
    (net (code "57") (name "Net-(T3A-C)") (class "Default")
      (node (ref "R6") (pin "2") (pinfunction "2_2") (pintype "passive"))
      (node (ref "T3") (pin "6") (pinfunction "C_6") (pintype "passive"))
    )
    (net (code "58") (name "Net-(T3B-B)") (class "Default")
      (node (ref "R15") (pin "2") (pinfunction "2_2") (pintype "passive"))
      (node (ref "T3") (pin "5") (pinfunction "B_5") (pintype "passive"))
    )
    (net (code "59") (name "Net-(T3B-C)") (class "Default")
      (node (ref "R25") (pin "2") (pinfunction "2_2") (pintype "passive"))
      (node (ref "T3") (pin "3") (pinfunction "C_3") (pintype "passive"))
    )
    (net (code "60") (name "P3V3") (class "Default")
      (node (ref "C29") (pin "2") (pinfunction "2_2") (pintype "passive"))
      (node (ref "C32") (pin "2") (pinfunction "2_2") (pintype "passive"))
      (node (ref "L2") (pin "1") (pinfunction "1_1") (pintype "passive"))
      (node (ref "L4") (pin "1") (pinfunction "1_1") (pintype "passive"))
      (node (ref "R41") (pin "2") (pinfunction "2_2") (pintype "passive"))
      (node (ref "R42") (pin "2") (pinfunction "2_2") (pintype "passive"))
      (node (ref "R43") (pin "2") (pinfunction "2_2") (pintype "passive"))
      (node (ref "R44") (pin "2") (pinfunction "2_2") (pintype "passive"))
      (node (ref "R45") (pin "2") (pinfunction "2_2") (pintype "passive"))
      (node (ref "R46") (pin "2") (pinfunction "2_2") (pintype "passive"))
      (node (ref "T1") (pin "1") (pinfunction "E_1") (pintype "passive"))
      (node (ref "T1") (pin "4") (pinfunction "E_4") (pintype "passive"))
      (node (ref "T2") (pin "1") (pinfunction "E_1") (pintype "passive"))
      (node (ref "T2") (pin "4") (pinfunction "E_4") (pintype "passive"))
      (node (ref "T3") (pin "1") (pinfunction "E_1") (pintype "passive"))
      (node (ref "T3") (pin "4") (pinfunction "E_4") (pintype "passive"))
    )
    (net (code "61") (name "P5V0") (class "Default")
      (node (ref "C17") (pin "2") (pinfunction "2_2") (pintype "passive"))
      (node (ref "C18") (pin "2") (pinfunction "2_2") (pintype "passive"))
      (node (ref "C23") (pin "2") (pinfunction "2_2") (pintype "passive"))
      (node (ref "L10") (pin "2") (pinfunction "2_2") (pintype "passive"))
    )
    (net (code "62") (name "unconnected-(IC1-NC-Pad3)") (class "Default")
      (node (ref "IC1") (pin "3") (pinfunction "NC_3") (pintype "passive+no_connect"))
    )
    (net (code "63") (name "unconnected-(IC1-NC-Pad4)") (class "Default")
      (node (ref "IC1") (pin "4") (pinfunction "NC_4") (pintype "passive+no_connect"))
    )
    (net (code "64") (name "unconnected-(IC2-QH'-Pad9)") (class "Default")
      (node (ref "IC2") (pin "9") (pinfunction "QH'_9") (pintype "output+no_connect"))
    )
    (net (code "65") (name "unconnected-(IC4-N{slash}C-Pad13)") (class "Default")
      (node (ref "IC4") (pin "13") (pinfunction "N/C_13") (pintype "passive+no_connect"))
    )
    (net (code "66") (name "unconnected-(IC4-N{slash}C-Pad14)") (class "Default")
      (node (ref "IC4") (pin "14") (pinfunction "N/C_14") (pintype "passive+no_connect"))
    )
    (net (code "67") (name "unconnected-(IC4-N{slash}C-Pad16)") (class "Default")
      (node (ref "IC4") (pin "16") (pinfunction "N/C_16") (pintype "passive+no_connect"))
    )
  )
)
